# ai_breakout_LSM9DS0.net
KiCad netlist of a schematic drawn in EAGLE
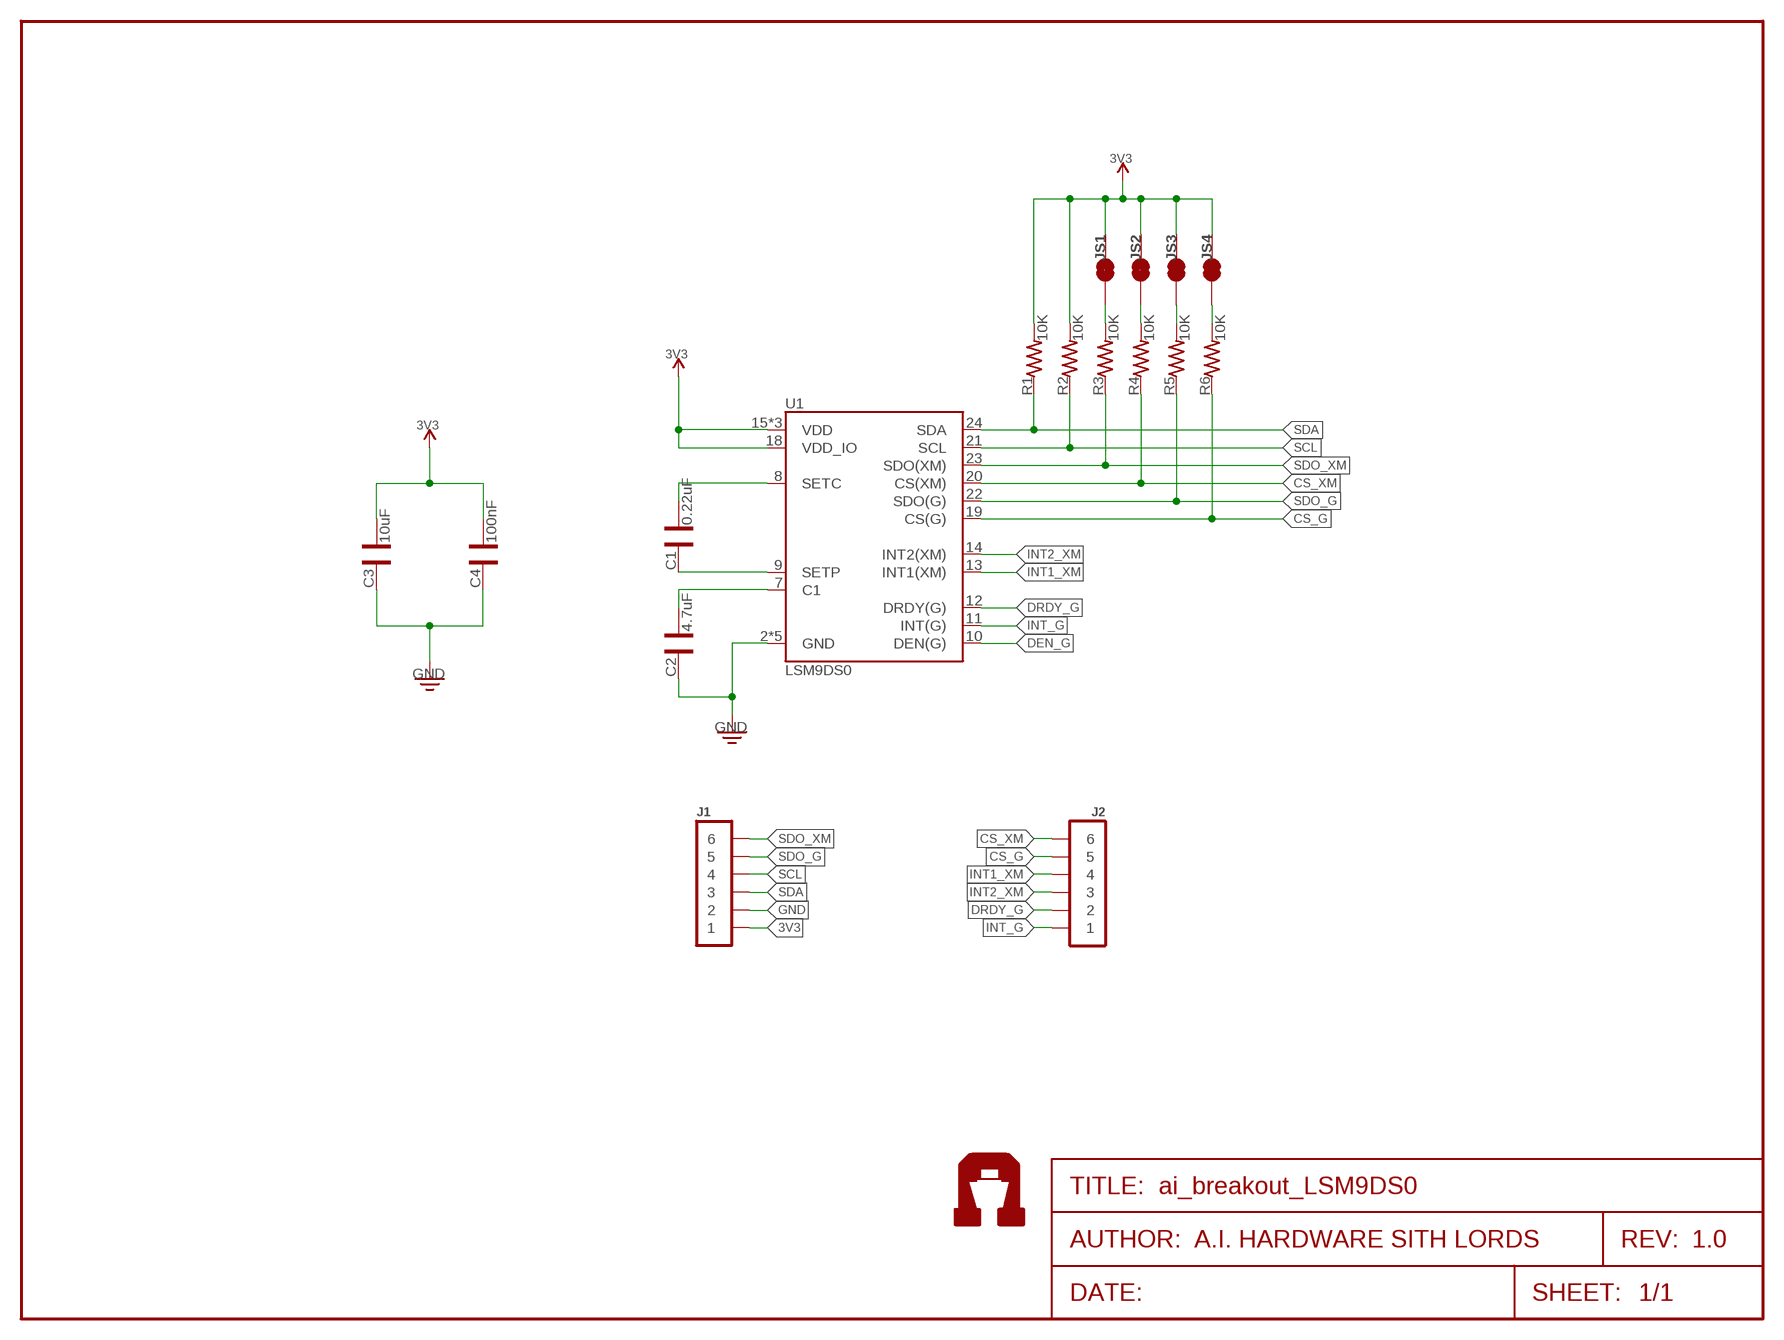
[diagram p0: schematic, sheet 1]

(export (version "E")
  (design (tool "Eeschema 10.0.6"))
  (components
    (comp (ref "C1")
      (value "0.22uF")
      (footprint "eagle-import:CAP-0603")
      (libsource (lib "eagle-import") (part "CAP0603"))
    )
    (comp (ref "C2")
      (value "4.7uF")
      (footprint "eagle-import:CAP-0603")
      (libsource (lib "eagle-import") (part "CAP0603"))
    )
    (comp (ref "C3")
      (value "10uF")
      (footprint "eagle-import:CAP-0603")
      (libsource (lib "eagle-import") (part "CAP0603"))
    )
    (comp (ref "C4")
      (value "100nF")
      (footprint "eagle-import:CAP-0603")
      (libsource (lib "eagle-import") (part "CAP0603"))
    )
    (comp (ref "J1")
      (value "1X06")
      (footprint "eagle-import:1X06")
      (libsource (lib "eagle-import") (part "1X06"))
    )
    (comp (ref "J2")
      (value "1X06NOFIRST")
      (footprint "eagle-import:1X06-NOFIRST")
      (libsource (lib "eagle-import") (part "1X06NOFIRST"))
    )
    (comp (ref "JS1")
      (value "1X02-SJ-NCT")
      (footprint "eagle-import:1X02-SJ-NCT")
      (libsource (lib "eagle-import") (part "1X02-SJ-NCT"))
    )
    (comp (ref "JS2")
      (value "1X02-SJ-NCT")
      (footprint "eagle-import:1X02-SJ-NCT")
      (libsource (lib "eagle-import") (part "1X02-SJ-NCT"))
    )
    (comp (ref "JS3")
      (value "1X02-SJ-NCT")
      (footprint "eagle-import:1X02-SJ-NCT")
      (libsource (lib "eagle-import") (part "1X02-SJ-NCT"))
    )
    (comp (ref "JS4")
      (value "1X02-SJ-NCT")
      (footprint "eagle-import:1X02-SJ-NCT")
      (libsource (lib "eagle-import") (part "1X02-SJ-NCT"))
    )
    (comp (ref "R1")
      (value "10K")
      (footprint "eagle-import:RES-0603")
      (libsource (lib "eagle-import") (part "RES0603"))
    )
    (comp (ref "R2")
      (value "10K")
      (footprint "eagle-import:RES-0603")
      (libsource (lib "eagle-import") (part "RES0603"))
    )
    (comp (ref "R3")
      (value "10K")
      (footprint "eagle-import:RES-0603")
      (libsource (lib "eagle-import") (part "RES0603"))
    )
    (comp (ref "R4")
      (value "10K")
      (footprint "eagle-import:RES-0603")
      (libsource (lib "eagle-import") (part "RES0603"))
    )
    (comp (ref "R5")
      (value "10K")
      (footprint "eagle-import:RES-0603")
      (libsource (lib "eagle-import") (part "RES0603"))
    )
    (comp (ref "R6")
      (value "10K")
      (footprint "eagle-import:RES-0603")
      (libsource (lib "eagle-import") (part "RES0603"))
    )
    (comp (ref "U$4")
      (value "AI-LOGOXS")
      (footprint "eagle-import:AI-LOGO-XS")
      (libsource (lib "eagle-import") (part "AI-LOGOXS"))
    )
    (comp (ref "U1")
      (value "LSM9DS0")
      (footprint "eagle-import:LGA-24")
      (libsource (lib "eagle-import") (part "LSM9DS0"))
    )
  )
  (nets
    (net (code "1") (name "3V3") (class "Default")
      (node (ref "C3") (pin "1") (pinfunction "1_1") (pintype "passive"))
      (node (ref "C4") (pin "1") (pinfunction "1_1") (pintype "passive"))
      (node (ref "J1") (pin "1") (pinfunction "1_1") (pintype "bidirectional"))
      (node (ref "JS1") (pin "2") (pinfunction "2_2") (pintype "passive"))
      (node (ref "JS2") (pin "2") (pinfunction "2_2") (pintype "passive"))
      (node (ref "JS3") (pin "2") (pinfunction "2_2") (pintype "passive"))
      (node (ref "JS4") (pin "2") (pinfunction "2_2") (pintype "passive"))
      (node (ref "R1") (pin "2") (pinfunction "2_2") (pintype "passive"))
      (node (ref "R2") (pin "2") (pinfunction "2_2") (pintype "passive"))
      (node (ref "U1") (pin "15") (pinfunction "VDD_15") (pintype "bidirectional"))
      (node (ref "U1") (pin "16") (pinfunction "VDD_16") (pintype "bidirectional"))
      (node (ref "U1") (pin "17") (pinfunction "VDD_17") (pintype "bidirectional"))
      (node (ref "U1") (pin "18") (pinfunction "VDD_IO_18") (pintype "bidirectional"))
    )
    (net (code "2") (name "CS_G") (class "Default")
      (node (ref "J2") (pin "5") (pinfunction "5_5") (pintype "bidirectional"))
      (node (ref "R6") (pin "1") (pinfunction "1_1") (pintype "passive"))
      (node (ref "U1") (pin "19") (pinfunction "CS(G)_19") (pintype "bidirectional"))
    )
    (net (code "3") (name "CS_XM") (class "Default")
      (node (ref "J2") (pin "6") (pinfunction "6_6") (pintype "bidirectional"))
      (node (ref "R4") (pin "1") (pinfunction "1_1") (pintype "passive"))
      (node (ref "U1") (pin "20") (pinfunction "CS(XM)_20") (pintype "bidirectional"))
    )
    (net (code "4") (name "DEN_G") (class "Default")
      (node (ref "U1") (pin "10") (pinfunction "DEN(G)_10") (pintype "bidirectional"))
    )
    (net (code "5") (name "DRDY_G") (class "Default")
      (node (ref "J2") (pin "2") (pinfunction "2_2") (pintype "bidirectional"))
      (node (ref "U1") (pin "12") (pinfunction "DRDY(G)_12") (pintype "bidirectional"))
    )
    (net (code "6") (name "GND") (class "Default")
      (node (ref "C2") (pin "2") (pinfunction "2_2") (pintype "passive"))
      (node (ref "C3") (pin "2") (pinfunction "2_2") (pintype "passive"))
      (node (ref "C4") (pin "2") (pinfunction "2_2") (pintype "passive"))
      (node (ref "J1") (pin "2") (pinfunction "2_2") (pintype "bidirectional"))
      (node (ref "U1") (pin "2") (pinfunction "GND_2") (pintype "bidirectional"))
      (node (ref "U1") (pin "3") (pinfunction "GND_3") (pintype "bidirectional"))
      (node (ref "U1") (pin "4") (pinfunction "GND_4") (pintype "bidirectional"))
      (node (ref "U1") (pin "5") (pinfunction "GND_5") (pintype "bidirectional"))
      (node (ref "U1") (pin "6") (pinfunction "GND_6") (pintype "bidirectional"))
    )
    (net (code "7") (name "INT1_XM") (class "Default")
      (node (ref "J2") (pin "4") (pinfunction "4_4") (pintype "bidirectional"))
      (node (ref "U1") (pin "13") (pinfunction "INT1(XM)_13") (pintype "bidirectional"))
    )
    (net (code "8") (name "INT2_XM") (class "Default")
      (node (ref "J2") (pin "3") (pinfunction "3_3") (pintype "bidirectional"))
      (node (ref "U1") (pin "14") (pinfunction "INT2(XM)_14") (pintype "bidirectional"))
    )
    (net (code "9") (name "INT_G") (class "Default")
      (node (ref "J2") (pin "1") (pinfunction "1_1") (pintype "bidirectional"))
      (node (ref "U1") (pin "11") (pinfunction "INT(G)_11") (pintype "bidirectional"))
    )
    (net (code "10") (name "Net-(JS1-Pad1)") (class "Default")
      (node (ref "JS1") (pin "1") (pinfunction "1_1") (pintype "passive"))
      (node (ref "R3") (pin "2") (pinfunction "2_2") (pintype "passive"))
    )
    (net (code "11") (name "Net-(JS2-Pad1)") (class "Default")
      (node (ref "JS2") (pin "1") (pinfunction "1_1") (pintype "passive"))
      (node (ref "R4") (pin "2") (pinfunction "2_2") (pintype "passive"))
    )
    (net (code "12") (name "Net-(JS3-Pad1)") (class "Default")
      (node (ref "JS3") (pin "1") (pinfunction "1_1") (pintype "passive"))
      (node (ref "R5") (pin "2") (pinfunction "2_2") (pintype "passive"))
    )
    (net (code "13") (name "Net-(JS4-Pad1)") (class "Default")
      (node (ref "JS4") (pin "1") (pinfunction "1_1") (pintype "passive"))
      (node (ref "R6") (pin "2") (pinfunction "2_2") (pintype "passive"))
    )
    (net (code "14") (name "Net-(U1-C1)") (class "Default")
      (node (ref "C2") (pin "1") (pinfunction "1_1") (pintype "passive"))
      (node (ref "U1") (pin "7") (pinfunction "C1_7") (pintype "bidirectional"))
    )
    (net (code "15") (name "Net-(U1-SETC)") (class "Default")
      (node (ref "C1") (pin "1") (pinfunction "1_1") (pintype "passive"))
      (node (ref "U1") (pin "8") (pinfunction "SETC_8") (pintype "bidirectional"))
    )
    (net (code "16") (name "Net-(U1-SETP)") (class "Default")
      (node (ref "C1") (pin "2") (pinfunction "2_2") (pintype "passive"))
      (node (ref "U1") (pin "9") (pinfunction "SETP_9") (pintype "bidirectional"))
    )
    (net (code "17") (name "SCL") (class "Default")
      (node (ref "J1") (pin "4") (pinfunction "4_4") (pintype "bidirectional"))
      (node (ref "R2") (pin "1") (pinfunction "1_1") (pintype "passive"))
      (node (ref "U1") (pin "21") (pinfunction "SCL_21") (pintype "bidirectional"))
    )
    (net (code "18") (name "SDA") (class "Default")
      (node (ref "J1") (pin "3") (pinfunction "3_3") (pintype "bidirectional"))
      (node (ref "R1") (pin "1") (pinfunction "1_1") (pintype "passive"))
      (node (ref "U1") (pin "24") (pinfunction "SDA_24") (pintype "bidirectional"))
    )
    (net (code "19") (name "SDO_G") (class "Default")
      (node (ref "J1") (pin "5") (pinfunction "5_5") (pintype "bidirectional"))
      (node (ref "R5") (pin "1") (pinfunction "1_1") (pintype "passive"))
      (node (ref "U1") (pin "22") (pinfunction "SDO(G)_22") (pintype "bidirectional"))
    )
    (net (code "20") (name "SDO_XM") (class "Default")
      (node (ref "J1") (pin "6") (pinfunction "6_6") (pintype "bidirectional"))
      (node (ref "R3") (pin "1") (pinfunction "1_1") (pintype "passive"))
      (node (ref "U1") (pin "23") (pinfunction "SDO(XM)_23") (pintype "bidirectional"))
    )
  )
)
